# PowerMonitor.net
KiCad netlist of a schematic drawn in Altium Designer
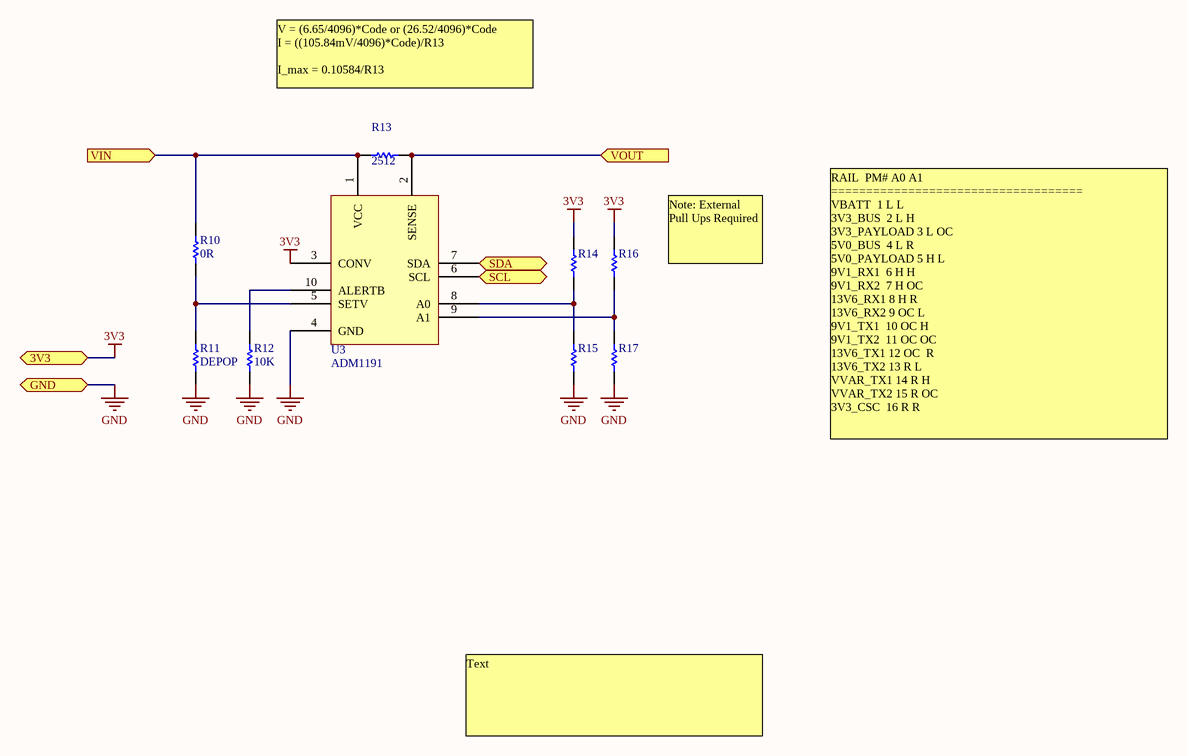
[diagram p0: PowerMonitor.SchDoc]

(export (version "E")
  (design (tool "Eeschema 10.0.6"))
  (components
    (comp (ref "R10")
      (value "0R")
      (footprint "R0402M")
      (description "Resistor")
      (fields (field (name "PUBLISHER") "Altium Limited"))
      (libsource (lib "Miscellaneous Devices") (part "Res1"))
    )
    (comp (ref "R11")
      (value "DEPOP")
      (footprint "R0402M")
      (description "Resistor")
      (fields (field (name "PUBLISHER") "Altium Limited"))
      (libsource (lib "Miscellaneous Devices") (part "Res1"))
    )
    (comp (ref "R12")
      (value "10K")
      (footprint "R0402M")
      (description "Resistor")
      (fields (field (name "PUBLISHER") "Altium Limited"))
      (libsource (lib "Miscellaneous Devices") (part "Res1"))
    )
    (comp (ref "R13")
      (value "~")
      (footprint "2512")
      (description "Resistor")
      (fields (field (name "PUBLISHER") "Altium Limited"))
      (libsource (lib "Miscellaneous Devices") (part "Res1"))
    )
    (comp (ref "R14")
      (value "~")
      (footprint "R0402M")
      (description "Resistor")
      (fields (field (name "PUBLISHER") "Altium Limited"))
      (libsource (lib "Miscellaneous Devices") (part "Res1"))
    )
    (comp (ref "R15")
      (value "~")
      (footprint "R0402M")
      (description "Resistor")
      (fields (field (name "PUBLISHER") "Altium Limited"))
      (libsource (lib "Miscellaneous Devices") (part "Res1"))
    )
    (comp (ref "R16")
      (value "~")
      (footprint "R0402M")
      (description "Resistor")
      (fields (field (name "PUBLISHER") "Altium Limited"))
      (libsource (lib "Miscellaneous Devices") (part "Res1"))
    )
    (comp (ref "R17")
      (value "~")
      (footprint "R0402M")
      (description "Resistor")
      (fields (field (name "PUBLISHER") "Altium Limited"))
      (libsource (lib "Miscellaneous Devices") (part "Res1"))
    )
    (comp (ref "U3") (value "ADM1191") (footprint "ADM1191") (libsource (lib "Tray2Mobo") (part "ADM1191")))
  )
  (nets
    (net (code "1") (name "/SCL") (class "Default")
      (node (ref "U3") (pin "6") (pinfunction "SCL_6") (pintype "passive"))
    )
    (net (code "2") (name "/SDA") (class "Default")
      (node (ref "U3") (pin "7") (pinfunction "SDA_7") (pintype "passive"))
    )
    (net (code "3") (name "/VIN") (class "Default")
      (node (ref "R10") (pin "1") (pinfunction "1_1") (pintype "passive"))
      (node (ref "R13") (pin "2") (pinfunction "2_2") (pintype "passive"))
      (node (ref "U3") (pin "1") (pinfunction "VCC_1") (pintype "passive"))
    )
    (net (code "4") (name "/VOUT") (class "Default")
      (node (ref "R13") (pin "1") (pinfunction "1_1") (pintype "passive"))
      (node (ref "U3") (pin "2") (pinfunction "SENSE_2") (pintype "passive"))
    )
    (net (code "5") (name "3V3") (class "Default")
      (node (ref "R14") (pin "1") (pinfunction "1_1") (pintype "passive"))
      (node (ref "R16") (pin "1") (pinfunction "1_1") (pintype "passive"))
      (node (ref "U3") (pin "3") (pinfunction "CONV_3") (pintype "passive"))
    )
    (net (code "6") (name "GND") (class "Default")
      (node (ref "R11") (pin "2") (pinfunction "2_2") (pintype "passive"))
      (node (ref "R12") (pin "2") (pinfunction "2_2") (pintype "passive"))
      (node (ref "R15") (pin "2") (pinfunction "2_2") (pintype "passive"))
      (node (ref "R17") (pin "2") (pinfunction "2_2") (pintype "passive"))
      (node (ref "U3") (pin "4") (pinfunction "GND_4") (pintype "passive"))
    )
    (net (code "7") (name "Net-(U3-A0)") (class "Default")
      (node (ref "R14") (pin "2") (pinfunction "2_2") (pintype "passive"))
      (node (ref "R15") (pin "1") (pinfunction "1_1") (pintype "passive"))
      (node (ref "U3") (pin "8") (pinfunction "A0_8") (pintype "passive"))
    )
    (net (code "8") (name "Net-(U3-A1)") (class "Default")
      (node (ref "R16") (pin "2") (pinfunction "2_2") (pintype "passive"))
      (node (ref "R17") (pin "1") (pinfunction "1_1") (pintype "passive"))
      (node (ref "U3") (pin "9") (pinfunction "A1_9") (pintype "passive"))
    )
    (net (code "9") (name "Net-(U3-ALERTB)") (class "Default")
      (node (ref "R12") (pin "1") (pinfunction "1_1") (pintype "passive"))
      (node (ref "U3") (pin "10") (pinfunction "ALERTB_10") (pintype "passive"))
    )
    (net (code "10") (name "Net-(U3-SETV)") (class "Default")
      (node (ref "R10") (pin "2") (pinfunction "2_2") (pintype "passive"))
      (node (ref "R11") (pin "1") (pinfunction "1_1") (pintype "passive"))
      (node (ref "U3") (pin "5") (pinfunction "SETV_5") (pintype "passive"))
    )
  )
)
